# ATSAMD09C_Breakout.net
KiCad netlist of a schematic drawn in EAGLE
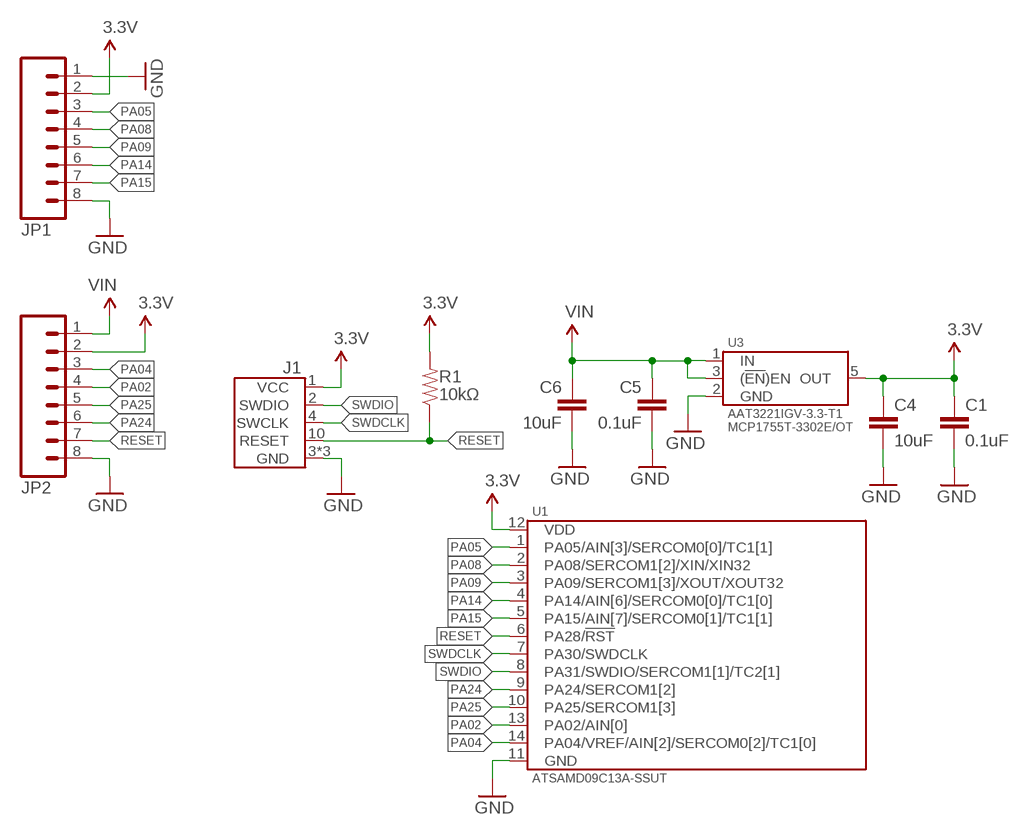
[diagram p0: schematic, sheet 1]

(export (version "E")
  (design (tool "Eeschema 10.0.6"))
  (components
    (comp (ref "C1")
      (value "0.1uF")
      (footprint "eagle-import:0805-CAP")
      (libsource (lib "eagle-import") (part "CAP-0805"))
    )
    (comp (ref "C4")
      (value "10uF")
      (footprint "eagle-import:0805-CAP")
      (libsource (lib "eagle-import") (part "CAP-0805"))
    )
    (comp (ref "C5")
      (value "0.1uF")
      (footprint "eagle-import:0805-CAP")
      (libsource (lib "eagle-import") (part "CAP-0805"))
    )
    (comp (ref "C6")
      (value "10uF")
      (footprint "eagle-import:0805-CAP")
      (libsource (lib "eagle-import") (part "CAP-0805"))
    )
    (comp (ref "J1")
      (value "SWD-50MIL-SHROUDED")
      (footprint "eagle-import:M05X2_50MIL_SHROUDED")
      (libsource (lib "eagle-import") (part "SWD-50MIL-SHROUDED"))
    )
    (comp (ref "JP1")
      (value "M08NO_SILK")
      (footprint "eagle-import:1X08_NO_SILK")
      (libsource (lib "eagle-import") (part "M08NO_SILK"))
    )
    (comp (ref "JP2")
      (value "M08NO_SILK")
      (footprint "eagle-import:1X08_NO_SILK")
      (libsource (lib "eagle-import") (part "M08NO_SILK"))
    )
    (comp (ref "R1")
      (value "10kΩ")
      (footprint "eagle-import:0805-RES")
      (libsource (lib "eagle-import") (part "RESISTOR-0805"))
    )
    (comp (ref "U1")
      (value "ATSAMD09C13A-SSUT")
      (footprint "eagle-import:SOIC-14")
      (libsource (lib "eagle-import") (part "ATSAMD09C13A-SSUT"))
    )
    (comp (ref "U3")
      (value "AAT3221IGV-3.3-T1")
      (footprint "eagle-import:SOT23-5")
      (libsource (lib "eagle-import") (part "AAT3221IGV-3.3-T1"))
    )
  )
  (nets
    (net (code "1") (name "3.3V") (class "Default")
      (node (ref "C1") (pin "1") (pinfunction "1_1") (pintype "passive"))
      (node (ref "C4") (pin "1") (pinfunction "1_1") (pintype "passive"))
      (node (ref "J1") (pin "1") (pinfunction "VCC_1") (pintype "bidirectional"))
      (node (ref "JP1") (pin "2") (pinfunction "2_2") (pintype "passive"))
      (node (ref "JP2") (pin "2") (pinfunction "2_2") (pintype "passive"))
      (node (ref "R1") (pin "2") (pinfunction "2_2") (pintype "passive"))
      (node (ref "U1") (pin "12") (pinfunction "VDD_12") (pintype "bidirectional"))
      (node (ref "U3") (pin "5") (pinfunction "OUT_5") (pintype "bidirectional"))
    )
    (net (code "2") (name "GND") (class "Default")
      (node (ref "C1") (pin "2") (pinfunction "2_2") (pintype "passive"))
      (node (ref "C4") (pin "2") (pinfunction "2_2") (pintype "passive"))
      (node (ref "C5") (pin "2") (pinfunction "2_2") (pintype "passive"))
      (node (ref "C6") (pin "2") (pinfunction "2_2") (pintype "passive"))
      (node (ref "J1") (pin "3") (pinfunction "GND_3") (pintype "bidirectional"))
      (node (ref "J1") (pin "5") (pinfunction "GND_5") (pintype "bidirectional"))
      (node (ref "J1") (pin "9") (pinfunction "GND_9") (pintype "bidirectional"))
      (node (ref "JP1") (pin "1") (pinfunction "1_1") (pintype "passive"))
      (node (ref "JP1") (pin "8") (pinfunction "8_8") (pintype "passive"))
      (node (ref "JP2") (pin "8") (pinfunction "8_8") (pintype "passive"))
      (node (ref "U1") (pin "11") (pinfunction "GND_11") (pintype "bidirectional"))
      (node (ref "U3") (pin "2") (pinfunction "GND_2") (pintype "bidirectional"))
    )
    (net (code "3") (name "PA02") (class "Default")
      (node (ref "JP2") (pin "4") (pinfunction "4_4") (pintype "passive"))
      (node (ref "U1") (pin "13") (pinfunction "PA02/AIN[0]_13") (pintype "bidirectional"))
    )
    (net (code "4") (name "PA04") (class "Default")
      (node (ref "JP2") (pin "3") (pinfunction "3_3") (pintype "passive"))
      (node (ref "U1") (pin "14") (pinfunction "PA04/VREF/AIN[2]/SERCOM0[2]/TC1[0]_14") (pintype "bidirectional"))
    )
    (net (code "5") (name "PA05") (class "Default")
      (node (ref "JP1") (pin "3") (pinfunction "3_3") (pintype "passive"))
      (node (ref "U1") (pin "1") (pinfunction "PA05/AIN[3]/SERCOM0[0]/TC1[1]_1") (pintype "bidirectional"))
    )
    (net (code "6") (name "PA08") (class "Default")
      (node (ref "JP1") (pin "4") (pinfunction "4_4") (pintype "passive"))
      (node (ref "U1") (pin "2") (pinfunction "PA08/SERCOM1[2]/XIN/XIN32_2") (pintype "bidirectional"))
    )
    (net (code "7") (name "PA09") (class "Default")
      (node (ref "JP1") (pin "5") (pinfunction "5_5") (pintype "passive"))
      (node (ref "U1") (pin "3") (pinfunction "PA09/SERCOM1[3]/XOUT/XOUT32_3") (pintype "bidirectional"))
    )
    (net (code "8") (name "PA14") (class "Default")
      (node (ref "JP1") (pin "6") (pinfunction "6_6") (pintype "passive"))
      (node (ref "U1") (pin "4") (pinfunction "PA14/AIN[6]/SERCOM0[0]/TC1[0]_4") (pintype "bidirectional"))
    )
    (net (code "9") (name "PA15") (class "Default")
      (node (ref "JP1") (pin "7") (pinfunction "7_7") (pintype "passive"))
      (node (ref "U1") (pin "5") (pinfunction "PA15/AIN[7]/SERCOM0[1]/TC1[1]_5") (pintype "bidirectional"))
    )
    (net (code "10") (name "PA24") (class "Default")
      (node (ref "JP2") (pin "6") (pinfunction "6_6") (pintype "passive"))
      (node (ref "U1") (pin "9") (pinfunction "PA24/SERCOM1[2]_9") (pintype "bidirectional"))
    )
    (net (code "11") (name "PA25") (class "Default")
      (node (ref "JP2") (pin "5") (pinfunction "5_5") (pintype "passive"))
      (node (ref "U1") (pin "10") (pinfunction "PA25/SERCOM1[3]_10") (pintype "bidirectional"))
    )
    (net (code "12") (name "RESET") (class "Default")
      (node (ref "J1") (pin "10") (pinfunction "RESET_10") (pintype "bidirectional"))
      (node (ref "JP2") (pin "7") (pinfunction "7_7") (pintype "passive"))
      (node (ref "R1") (pin "1") (pinfunction "1_1") (pintype "passive"))
      (node (ref "U1") (pin "6") (pinfunction "PA28/~{RST}_6") (pintype "bidirectional"))
    )
    (net (code "13") (name "SWDCLK") (class "Default")
      (node (ref "J1") (pin "4") (pinfunction "SWCLK_4") (pintype "bidirectional"))
      (node (ref "U1") (pin "7") (pinfunction "PA30/SWDCLK_7") (pintype "bidirectional"))
    )
    (net (code "14") (name "SWDIO") (class "Default")
      (node (ref "J1") (pin "2") (pinfunction "SWDIO_2") (pintype "bidirectional"))
      (node (ref "U1") (pin "8") (pinfunction "PA31/SWDIO/SERCOM1[1]/TC2[1]_8") (pintype "bidirectional"))
    )
    (net (code "15") (name "VIN") (class "Default")
      (node (ref "C5") (pin "1") (pinfunction "1_1") (pintype "passive"))
      (node (ref "C6") (pin "1") (pinfunction "1_1") (pintype "passive"))
      (node (ref "JP2") (pin "1") (pinfunction "1_1") (pintype "passive"))
      (node (ref "U3") (pin "1") (pinfunction "IN_1") (pintype "bidirectional"))
      (node (ref "U3") (pin "3") (pinfunction "(~{EN})EN_3") (pintype "bidirectional"))
    )
  )
)
